# MCU.net
KiCad netlist of a schematic drawn in Altium Designer
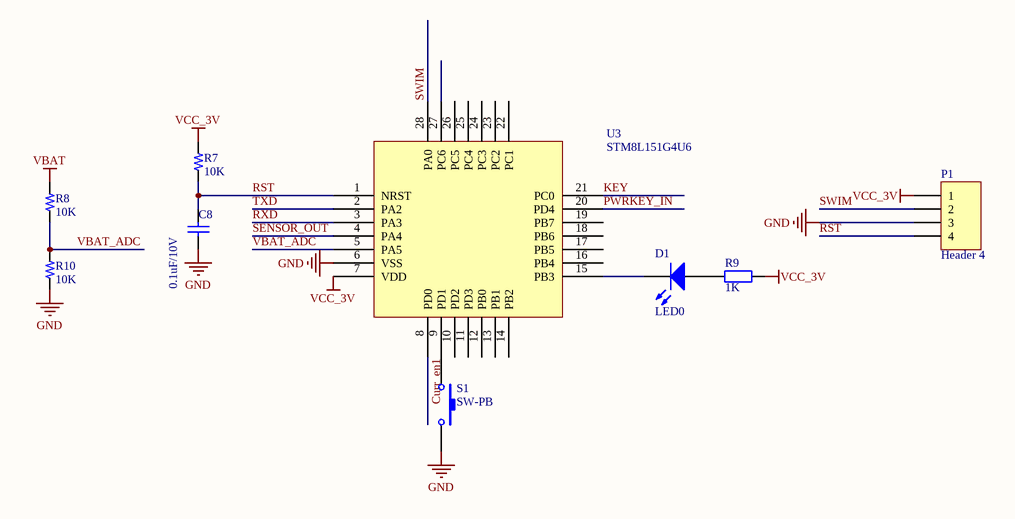
[diagram p0: MCU.SchDoc]

(export (version "E")
  (design (tool "Eeschema 10.0.6"))
  (components
    (comp (ref "C8")
      (value "0.1uF/10V")
      (footprint "0603C")
      (description "Capacitor")
      (fields (field (name "PUBLISHER") "Altium Limited"))
      (libsource (lib "Miscellaneous Devices") (part "Cap"))
    )
    (comp (ref "D1")
      (value "LED0")
      (footprint "0603LED")
      (description "Typical INFRARED GaAs LED")
      (fields (field (name "PUBLISHER") "Altium Limited"))
      (libsource (lib "Miscellaneous Devices") (part "LED0"))
    )
    (comp (ref "P1")
      (value "Header 4")
      (footprint "HDR1X4")
      (description "Header, 4-Pin")
      (fields (field (name "PUBLISHER") "Altium Limited"))
      (libsource (lib "Miscellaneous Connectors") (part "Header 4"))
    )
    (comp (ref "R7") (value "10K") (footprint "0603R") (description "R") (libsource (lib "JRJ_1") (part "R")))
    (comp (ref "R8") (value "10K") (footprint "0603R") (description "R") (libsource (lib "JRJ_1") (part "R")))
    (comp (ref "R9")
      (value "1K")
      (footprint "0603R")
      (description "Resistor")
      (fields (field (name "PUBLISHER") "Altium Limited"))
      (libsource (lib "Miscellaneous Devices") (part "Res2"))
    )
    (comp (ref "R10")
      (value "10K")
      (footprint "0603R")
      (description "R")
      (libsource (lib "JRJ_1") (part "R"))
    )
    (comp (ref "S1")
      (value "SW-PB")
      (footprint "key")
      (description "Switch")
      (fields (field (name "PUBLISHER") "Altium Limited"))
      (libsource (lib "Miscellaneous Devices") (part "SW-PB"))
    )
    (comp (ref "U3")
      (value "STM8L151G4U6")
      (footprint "QFP80P900X900X245-32N")
      (libsource (lib "Schlib_20110825") (part "STM8L151G4U6"))
    )
  )
  (nets
    (net (code "1") (name "/Curr_en1") (class "Default")
      (node (ref "U3") (pin "8") (pinfunction "PD0_8") (pintype "passive"))
    )
    (net (code "2") (name "/KEY") (class "Default")
      (node (ref "U3") (pin "21") (pinfunction "PC0_21") (pintype "passive"))
    )
    (net (code "3") (name "/PWRKEY_IN") (class "Default")
      (node (ref "U3") (pin "20") (pinfunction "PD4_20") (pintype "passive"))
    )
    (net (code "4") (name "/RST") (class "Default")
      (node (ref "C8") (pin "1") (pinfunction "1_1") (pintype "passive"))
      (node (ref "P1") (pin "4") (pinfunction "4_4") (pintype "passive"))
      (node (ref "R7") (pin "1") (pintype "passive"))
      (node (ref "U3") (pin "1") (pinfunction "NRST_1") (pintype "passive"))
    )
    (net (code "5") (name "/RXD") (class "Default")
      (node (ref "U3") (pin "3") (pinfunction "PA3_3") (pintype "passive"))
    )
    (net (code "6") (name "/SENSOR_OUT") (class "Default")
      (node (ref "U3") (pin "4") (pinfunction "PA4_4") (pintype "passive"))
    )
    (net (code "7") (name "/SWIM") (class "Default")
      (node (ref "P1") (pin "2") (pinfunction "2_2") (pintype "passive"))
      (node (ref "U3") (pin "28") (pinfunction "PA0_28") (pintype "passive"))
    )
    (net (code "8") (name "/TXD") (class "Default")
      (node (ref "U3") (pin "2") (pinfunction "PA2_2") (pintype "passive"))
    )
    (net (code "9") (name "/VBAT_ADC") (class "Default")
      (node (ref "R10") (pin "2") (pintype "passive"))
      (node (ref "R8") (pin "1") (pintype "passive"))
      (node (ref "U3") (pin "5") (pinfunction "PA5_5") (pintype "passive"))
    )
    (net (code "10") (name "GND") (class "Default")
      (node (ref "C8") (pin "2") (pinfunction "2_2") (pintype "passive"))
      (node (ref "P1") (pin "3") (pinfunction "3_3") (pintype "passive"))
      (node (ref "R10") (pin "1") (pintype "passive"))
      (node (ref "S1") (pin "2") (pinfunction "2_2") (pintype "passive"))
      (node (ref "U3") (pin "6") (pinfunction "VSS_6") (pintype "passive"))
    )
    (net (code "11") (name "Net-(D1-A)") (class "Default")
      (node (ref "D1") (pin "1") (pinfunction "A_1") (pintype "passive"))
      (node (ref "R9") (pin "2") (pinfunction "2_2") (pintype "passive"))
    )
    (net (code "12") (name "Net-(D1-K)") (class "Default")
      (node (ref "D1") (pin "2") (pinfunction "K_2") (pintype "passive"))
      (node (ref "U3") (pin "15") (pinfunction "PB3_15") (pintype "passive"))
    )
    (net (code "13") (name "Net-(U3-PD1)") (class "Default")
      (node (ref "S1") (pin "1") (pinfunction "1_1") (pintype "passive"))
      (node (ref "U3") (pin "9") (pinfunction "PD1_9") (pintype "passive"))
    )
    (net (code "14") (name "VBAT") (class "Default") (node (ref "R8") (pin "2") (pintype "passive")))
    (net (code "15") (name "VCC_3V") (class "Default")
      (node (ref "P1") (pin "1") (pinfunction "1_1") (pintype "passive"))
      (node (ref "R7") (pin "2") (pintype "passive"))
      (node (ref "R9") (pin "1") (pinfunction "1_1") (pintype "passive"))
      (node (ref "U3") (pin "7") (pinfunction "VDD_7") (pintype "passive"))
    )
    (net (code "16") (name "unconnected-(U3-PB0-Pad12)") (class "Default")
      (node (ref "U3") (pin "12") (pinfunction "PB0_12") (pintype "passive"))
    )
    (net (code "17") (name "unconnected-(U3-PB1-Pad13)") (class "Default")
      (node (ref "U3") (pin "13") (pinfunction "PB1_13") (pintype "passive"))
    )
    (net (code "18") (name "unconnected-(U3-PB2-Pad14)") (class "Default")
      (node (ref "U3") (pin "14") (pinfunction "PB2_14") (pintype "passive"))
    )
    (net (code "19") (name "unconnected-(U3-PB4-Pad16)") (class "Default")
      (node (ref "U3") (pin "16") (pinfunction "PB4_16") (pintype "passive"))
    )
    (net (code "20") (name "unconnected-(U3-PB5-Pad17)") (class "Default")
      (node (ref "U3") (pin "17") (pinfunction "PB5_17") (pintype "passive"))
    )
    (net (code "21") (name "unconnected-(U3-PB6-Pad18)") (class "Default")
      (node (ref "U3") (pin "18") (pinfunction "PB6_18") (pintype "passive"))
    )
    (net (code "22") (name "unconnected-(U3-PB7-Pad19)") (class "Default")
      (node (ref "U3") (pin "19") (pinfunction "PB7_19") (pintype "passive"))
    )
    (net (code "23") (name "unconnected-(U3-PC1-Pad22)") (class "Default")
      (node (ref "U3") (pin "22") (pinfunction "PC1_22") (pintype "passive"))
    )
    (net (code "24") (name "unconnected-(U3-PC2-Pad23)") (class "Default")
      (node (ref "U3") (pin "23") (pinfunction "PC2_23") (pintype "passive"))
    )
    (net (code "25") (name "unconnected-(U3-PC3-Pad24)") (class "Default")
      (node (ref "U3") (pin "24") (pinfunction "PC3_24") (pintype "passive"))
    )
    (net (code "26") (name "unconnected-(U3-PC4-Pad25)") (class "Default")
      (node (ref "U3") (pin "25") (pinfunction "PC4_25") (pintype "passive"))
    )
    (net (code "27") (name "unconnected-(U3-PC5-Pad26)") (class "Default")
      (node (ref "U3") (pin "26") (pinfunction "PC5_26") (pintype "passive"))
    )
    (net (code "28") (name "unconnected-(U3-PC6-Pad27)") (class "Default")
      (node (ref "U3") (pin "27") (pinfunction "PC6_27") (pintype "passive"))
    )
    (net (code "29") (name "unconnected-(U3-PD2-Pad10)") (class "Default")
      (node (ref "U3") (pin "10") (pinfunction "PD2_10") (pintype "passive"))
    )
    (net (code "30") (name "unconnected-(U3-PD3-Pad11)") (class "Default")
      (node (ref "U3") (pin "11") (pinfunction "PD3_11") (pintype "passive"))
    )
  )
)
